# blinky_Ahoura.net
KiCad netlist of a schematic drawn in EAGLE
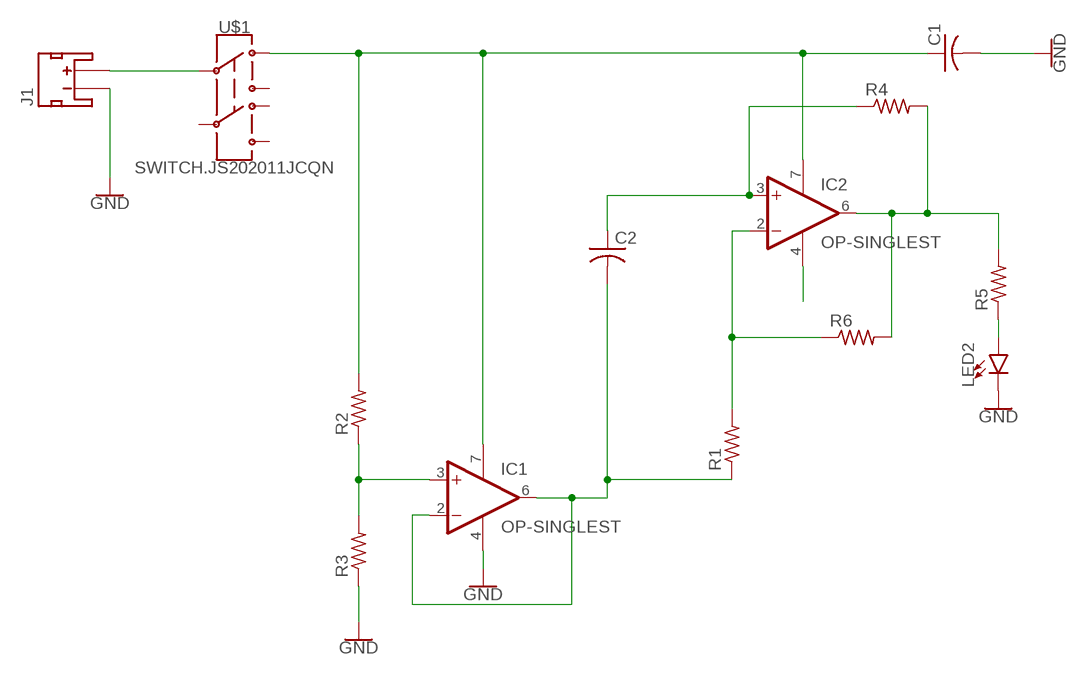
[diagram p0: schematic, sheet 1]

(export (version "E")
  (design (tool "Eeschema 10.0.6"))
  (components
    (comp (ref "C1")
      (value "C-USC0402")
      (footprint "eagle-import:C0402")
      (libsource (lib "eagle-import") (part "C-USC0402"))
    )
    (comp (ref "C2")
      (value "C-USC0402")
      (footprint "eagle-import:C0402")
      (libsource (lib "eagle-import") (part "C-USC0402"))
    )
    (comp (ref "IC1")
      (value "OP-SINGLEST")
      (footprint "eagle-import:TSSOP8")
      (libsource (lib "eagle-import") (part "OP-SINGLEST"))
    )
    (comp (ref "IC2")
      (value "OP-SINGLEST")
      (footprint "eagle-import:TSSOP8")
      (libsource (lib "eagle-import") (part "OP-SINGLEST"))
    )
    (comp (ref "J1")
      (value "JST_2MM_MALE")
      (footprint "eagle-import:JST-2-SMD")
      (libsource (lib "eagle-import") (part "JST_2MM_MALE"))
    )
    (comp (ref "LED2")
      (value "LED0603")
      (footprint "eagle-import:LED-0603")
      (libsource (lib "eagle-import") (part "LED0603"))
    )
    (comp (ref "R1")
      (value "R-US_R0402")
      (footprint "eagle-import:R0402")
      (libsource (lib "eagle-import") (part "R-US_R0402"))
    )
    (comp (ref "R2")
      (value "R-US_R0402")
      (footprint "eagle-import:R0402")
      (libsource (lib "eagle-import") (part "R-US_R0402"))
    )
    (comp (ref "R3")
      (value "R-US_R0402")
      (footprint "eagle-import:R0402")
      (libsource (lib "eagle-import") (part "R-US_R0402"))
    )
    (comp (ref "R4")
      (value "R-US_R0402")
      (footprint "eagle-import:R0402")
      (libsource (lib "eagle-import") (part "R-US_R0402"))
    )
    (comp (ref "R5")
      (value "R-US_R0402")
      (footprint "eagle-import:R0402")
      (libsource (lib "eagle-import") (part "R-US_R0402"))
    )
    (comp (ref "R6")
      (value "R-US_R0402")
      (footprint "eagle-import:R0402")
      (libsource (lib "eagle-import") (part "R-US_R0402"))
    )
    (comp (ref "U$1")
      (value "SWITCH.JS202011JCQN")
      (footprint "eagle-import:SWITCH.00")
      (libsource (lib "eagle-import") (part "SWITCH.JS202011JCQN"))
    )
  )
  (nets
    (net (code "1") (name "GND") (class "Default")
      (node (ref "C1") (pin "2") (pinfunction "2_2") (pintype "passive"))
      (node (ref "IC1") (pin "4") (pinfunction "V-_4") (pintype "power_in"))
      (node (ref "J1") (pin "1") (pinfunction "-_1") (pintype "bidirectional"))
      (node (ref "LED2") (pin "C") (pinfunction "C_C") (pintype "passive"))
      (node (ref "R3") (pin "1") (pinfunction "1_1") (pintype "passive"))
    )
    (net (code "2") (name "Net-(IC1-+IN)") (class "Default")
      (node (ref "IC1") (pin "3") (pinfunction "+IN_3") (pintype "input"))
      (node (ref "R2") (pin "1") (pinfunction "1_1") (pintype "passive"))
      (node (ref "R3") (pin "2") (pinfunction "2_2") (pintype "passive"))
    )
    (net (code "3") (name "Net-(IC1--IN)") (class "Default")
      (node (ref "C2") (pin "2") (pinfunction "2_2") (pintype "passive"))
      (node (ref "IC1") (pin "2") (pinfunction "-IN_2") (pintype "input"))
      (node (ref "IC1") (pin "6") (pinfunction "OUT_6") (pintype "output"))
      (node (ref "R1") (pin "1") (pinfunction "1_1") (pintype "passive"))
    )
    (net (code "4") (name "Net-(IC1-V+)") (class "Default")
      (node (ref "C1") (pin "1") (pinfunction "1_1") (pintype "passive"))
      (node (ref "IC1") (pin "7") (pinfunction "V+_7") (pintype "power_in"))
      (node (ref "IC2") (pin "7") (pinfunction "V+_7") (pintype "power_in"))
      (node (ref "R2") (pin "2") (pinfunction "2_2") (pintype "passive"))
      (node (ref "U$1") (pin "1") (pinfunction "1_1") (pintype "bidirectional"))
    )
    (net (code "5") (name "Net-(IC2-+IN)") (class "Default")
      (node (ref "C2") (pin "1") (pinfunction "1_1") (pintype "passive"))
      (node (ref "IC2") (pin "3") (pinfunction "+IN_3") (pintype "input"))
      (node (ref "R4") (pin "1") (pinfunction "1_1") (pintype "passive"))
    )
    (net (code "6") (name "Net-(IC2--IN)") (class "Default")
      (node (ref "IC2") (pin "2") (pinfunction "-IN_2") (pintype "input"))
      (node (ref "R1") (pin "2") (pinfunction "2_2") (pintype "passive"))
      (node (ref "R6") (pin "1") (pinfunction "1_1") (pintype "passive"))
    )
    (net (code "7") (name "Net-(IC2-OUT)") (class "Default")
      (node (ref "IC2") (pin "6") (pinfunction "OUT_6") (pintype "output"))
      (node (ref "R4") (pin "2") (pinfunction "2_2") (pintype "passive"))
      (node (ref "R5") (pin "2") (pinfunction "2_2") (pintype "passive"))
      (node (ref "R6") (pin "2") (pinfunction "2_2") (pintype "passive"))
    )
    (net (code "8") (name "Net-(J1-+)") (class "Default")
      (node (ref "J1") (pin "2") (pinfunction "+_2") (pintype "bidirectional"))
      (node (ref "U$1") (pin "2") (pinfunction "2_2") (pintype "bidirectional"))
    )
    (net (code "9") (name "Net-(LED2-PadA)") (class "Default")
      (node (ref "LED2") (pin "A") (pinfunction "A_A") (pintype "passive"))
      (node (ref "R5") (pin "1") (pinfunction "1_1") (pintype "passive"))
    )
    (net (code "10") (name "unconnected-(IC2-V--Pad4)") (class "Default")
      (node (ref "IC2") (pin "4") (pinfunction "V-_4") (pintype "power_in"))
    )
    (net (code "11") (name "unconnected-(J1-PAD1-PadNC1)") (class "Default")
      (node (ref "J1") (pin "NC1") (pinfunction "PAD1_NC1") (pintype "bidirectional"))
    )
    (net (code "12") (name "unconnected-(J1-PAD2-PadNC2)") (class "Default")
      (node (ref "J1") (pin "NC2") (pinfunction "PAD2_NC2") (pintype "bidirectional"))
    )
    (net (code "13") (name "unconnected-(U$1-Pad3)") (class "Default")
      (node (ref "U$1") (pin "3") (pinfunction "3_3") (pintype "bidirectional"))
    )
    (net (code "14") (name "unconnected-(U$1-Pad5)") (class "Default")
      (node (ref "U$1") (pin "5") (pinfunction "5_5") (pintype "bidirectional"))
    )
    (net (code "15") (name "unconnected-(U$1-Pad6)") (class "Default")
      (node (ref "U$1") (pin "6") (pinfunction "6_6") (pintype "bidirectional"))
    )
    (net (code "16") (name "unconnected-(U$1-Pad7)") (class "Default")
      (node (ref "U$1") (pin "7") (pinfunction "7_7") (pintype "bidirectional"))
    )
  )
)
